# AtmelSMD328NRF.net
KiCad netlist of a schematic drawn in EAGLE
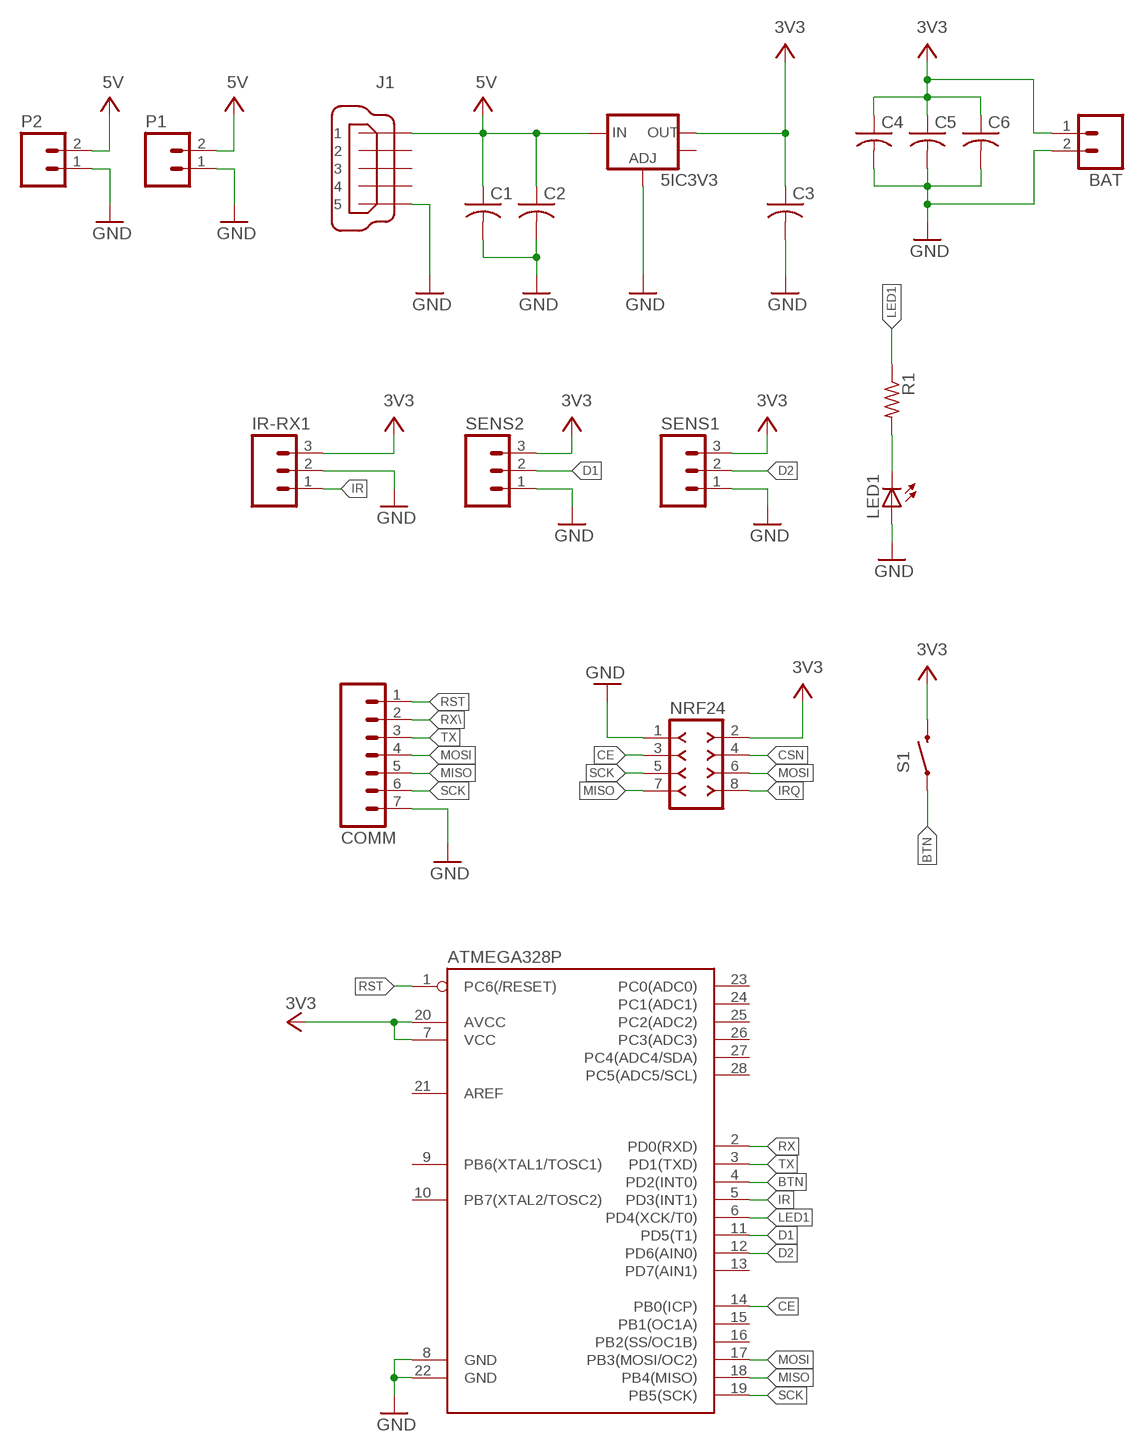
[diagram p0: schematic, sheet 1]

(export (version "E")
  (design (tool "Eeschema 10.0.6"))
  (components
    (comp (ref "5IC3V3")
      (value "V_REG_LM1117SOT223")
      (footprint "eagle-import:SOT223")
      (libsource (lib "eagle-import") (part "V_REG_LM1117SOT223"))
    )
    (comp (ref "ATMEGA328P")
      (value "ATMEGA328P_PDIP")
      (footprint "eagle-import:DIL28-3")
      (libsource (lib "eagle-import") (part "ATMEGA328P_PDIP"))
    )
    (comp (ref "BAT")
      (value "M02PTH")
      (footprint "eagle-import:1X02")
      (libsource (lib "eagle-import") (part "M02PTH"))
    )
    (comp (ref "C1")
      (value "C-USC0805")
      (footprint "eagle-import:C0805")
      (libsource (lib "eagle-import") (part "C-USC0805"))
    )
    (comp (ref "C2")
      (value "C-USC0805")
      (footprint "eagle-import:C0805")
      (libsource (lib "eagle-import") (part "C-USC0805"))
    )
    (comp (ref "C3")
      (value "C-USC0805")
      (footprint "eagle-import:C0805")
      (libsource (lib "eagle-import") (part "C-USC0805"))
    )
    (comp (ref "C4")
      (value "C-USC0805")
      (footprint "eagle-import:C0805")
      (libsource (lib "eagle-import") (part "C-USC0805"))
    )
    (comp (ref "C5")
      (value "C-USC0805")
      (footprint "eagle-import:C0805")
      (libsource (lib "eagle-import") (part "C-USC0805"))
    )
    (comp (ref "C6")
      (value "C-USC0805")
      (footprint "eagle-import:C0805")
      (libsource (lib "eagle-import") (part "C-USC0805"))
    )
    (comp (ref "COMM")
      (value "M07")
      (footprint "eagle-import:1X07")
      (libsource (lib "eagle-import") (part "M07"))
    )
    (comp (ref "IR-RX1")
      (value "M03PTH")
      (footprint "eagle-import:1X03")
      (libsource (lib "eagle-import") (part "M03PTH"))
    )
    (comp (ref "J1")
      (value "MICRO-USB-ZX62R-B-5P")
      (footprint "eagle-import:ZX62R-B-5P")
      (libsource (lib "eagle-import") (part "MICRO-USB-ZX62R-B-5P"))
    )
    (comp (ref "LED1")
      (value "LEDCHIPLED_0805")
      (footprint "eagle-import:CHIPLED_0805")
      (libsource (lib "eagle-import") (part "LEDCHIPLED_0805"))
    )
    (comp (ref "NRF24")
      (value "F-2X04-DIL-100")
      (footprint "eagle-import:DIL-100-2X04")
      (libsource (lib "eagle-import") (part "F-2X04-DIL-100"))
    )
    (comp (ref "P1")
      (value "M02PTH")
      (footprint "eagle-import:1X02")
      (libsource (lib "eagle-import") (part "M02PTH"))
    )
    (comp (ref "P2")
      (value "M02PTH")
      (footprint "eagle-import:1X02")
      (libsource (lib "eagle-import") (part "M02PTH"))
    )
    (comp (ref "R1")
      (value "R-US_R0805")
      (footprint "eagle-import:R0805")
      (libsource (lib "eagle-import") (part "R-US_R0805"))
    )
    (comp (ref "S1")
      (value "SWITCH-MOMENTARY-2SMD-1101NE")
      (footprint "eagle-import:TACTILE-SWITCH-1101NE")
      (libsource (lib "eagle-import") (part "SWITCH-MOMENTARY-2SMD-1101NE"))
    )
    (comp (ref "SENS1")
      (value "M03PTH")
      (footprint "eagle-import:1X03")
      (libsource (lib "eagle-import") (part "M03PTH"))
    )
    (comp (ref "SENS2")
      (value "M03PTH")
      (footprint "eagle-import:1X03")
      (libsource (lib "eagle-import") (part "M03PTH"))
    )
  )
  (nets
    (net (code "1") (name "3V3") (class "Default")
      (node (ref "5IC3V3") (pin "2") (pinfunction "OUT_2") (pintype "output"))
      (node (ref "ATMEGA328P") (pin "20") (pinfunction "AVCC_20") (pintype "bidirectional"))
      (node (ref "ATMEGA328P") (pin "7") (pinfunction "VCC_7") (pintype "bidirectional"))
      (node (ref "BAT") (pin "1") (pinfunction "1_1") (pintype "passive"))
      (node (ref "C3") (pin "1") (pinfunction "1_1") (pintype "passive"))
      (node (ref "C4") (pin "1") (pinfunction "1_1") (pintype "passive"))
      (node (ref "C5") (pin "1") (pinfunction "1_1") (pintype "passive"))
      (node (ref "C6") (pin "1") (pinfunction "1_1") (pintype "passive"))
      (node (ref "IR-RX1") (pin "3") (pinfunction "3_3") (pintype "passive"))
      (node (ref "NRF24") (pin "2") (pinfunction "2_2") (pintype "passive"))
      (node (ref "S1") (pin "2") (pinfunction "2_2") (pintype "passive"))
      (node (ref "SENS1") (pin "3") (pinfunction "3_3") (pintype "passive"))
      (node (ref "SENS2") (pin "3") (pinfunction "3_3") (pintype "passive"))
    )
    (net (code "2") (name "5V") (class "Default")
      (node (ref "5IC3V3") (pin "3") (pinfunction "IN_3") (pintype "input"))
      (node (ref "C1") (pin "1") (pinfunction "1_1") (pintype "passive"))
      (node (ref "C2") (pin "1") (pinfunction "1_1") (pintype "passive"))
      (node (ref "J1") (pin "1") (pinfunction "1_1") (pintype "input"))
      (node (ref "P1") (pin "2") (pinfunction "2_2") (pintype "passive"))
      (node (ref "P2") (pin "2") (pinfunction "2_2") (pintype "passive"))
    )
    (net (code "3") (name "BTN") (class "Default")
      (node (ref "ATMEGA328P") (pin "4") (pinfunction "PD2(INT0)_4") (pintype "bidirectional"))
      (node (ref "S1") (pin "1") (pinfunction "1_1") (pintype "passive"))
    )
    (net (code "4") (name "CE") (class "Default")
      (node (ref "ATMEGA328P") (pin "14") (pinfunction "PB0(ICP)_14") (pintype "bidirectional"))
      (node (ref "NRF24") (pin "3") (pinfunction "3_3") (pintype "passive"))
    )
    (net (code "5") (name "CSN") (class "Default")
      (node (ref "NRF24") (pin "4") (pinfunction "4_4") (pintype "passive"))
    )
    (net (code "6") (name "D1") (class "Default")
      (node (ref "ATMEGA328P") (pin "11") (pinfunction "PD5(T1)_11") (pintype "bidirectional"))
      (node (ref "SENS2") (pin "2") (pinfunction "2_2") (pintype "passive"))
    )
    (net (code "7") (name "D2") (class "Default")
      (node (ref "ATMEGA328P") (pin "12") (pinfunction "PD6(AIN0)_12") (pintype "bidirectional"))
      (node (ref "SENS1") (pin "2") (pinfunction "2_2") (pintype "passive"))
    )
    (net (code "8") (name "GND") (class "Default")
      (node (ref "5IC3V3") (pin "1") (pinfunction "ADJ_1") (pintype "input"))
      (node (ref "ATMEGA328P") (pin "22") (pinfunction "GND_22") (pintype "bidirectional"))
      (node (ref "ATMEGA328P") (pin "8") (pinfunction "GND_8") (pintype "bidirectional"))
      (node (ref "BAT") (pin "2") (pinfunction "2_2") (pintype "passive"))
      (node (ref "C1") (pin "2") (pinfunction "2_2") (pintype "passive"))
      (node (ref "C2") (pin "2") (pinfunction "2_2") (pintype "passive"))
      (node (ref "C3") (pin "2") (pinfunction "2_2") (pintype "passive"))
      (node (ref "C4") (pin "2") (pinfunction "2_2") (pintype "passive"))
      (node (ref "C5") (pin "2") (pinfunction "2_2") (pintype "passive"))
      (node (ref "C6") (pin "2") (pinfunction "2_2") (pintype "passive"))
      (node (ref "COMM") (pin "7") (pinfunction "7_7") (pintype "passive"))
      (node (ref "IR-RX1") (pin "2") (pinfunction "2_2") (pintype "passive"))
      (node (ref "J1") (pin "5") (pinfunction "5_5") (pintype "input"))
      (node (ref "LED1") (pin "A") (pinfunction "A_A") (pintype "passive"))
      (node (ref "NRF24") (pin "1") (pinfunction "1_1") (pintype "passive"))
      (node (ref "P1") (pin "1") (pinfunction "1_1") (pintype "passive"))
      (node (ref "P2") (pin "1") (pinfunction "1_1") (pintype "passive"))
      (node (ref "SENS1") (pin "1") (pinfunction "1_1") (pintype "passive"))
      (node (ref "SENS2") (pin "1") (pinfunction "1_1") (pintype "passive"))
    )
    (net (code "9") (name "IR") (class "Default")
      (node (ref "ATMEGA328P") (pin "5") (pinfunction "PD3(INT1)_5") (pintype "bidirectional"))
      (node (ref "IR-RX1") (pin "1") (pinfunction "1_1") (pintype "passive"))
    )
    (net (code "10") (name "IRQ") (class "Default")
      (node (ref "NRF24") (pin "8") (pinfunction "8_8") (pintype "passive"))
    )
    (net (code "11") (name "LED1") (class "Default")
      (node (ref "ATMEGA328P") (pin "6") (pinfunction "PD4(XCK/T0)_6") (pintype "bidirectional"))
      (node (ref "R1") (pin "1") (pinfunction "1_1") (pintype "passive"))
    )
    (net (code "12") (name "MISO") (class "Default")
      (node (ref "ATMEGA328P") (pin "18") (pinfunction "PB4(MISO)_18") (pintype "bidirectional"))
      (node (ref "COMM") (pin "5") (pinfunction "5_5") (pintype "passive"))
      (node (ref "NRF24") (pin "7") (pinfunction "7_7") (pintype "passive"))
    )
    (net (code "13") (name "MOSI") (class "Default")
      (node (ref "ATMEGA328P") (pin "17") (pinfunction "PB3(MOSI/OC2)_17") (pintype "bidirectional"))
      (node (ref "COMM") (pin "4") (pinfunction "4_4") (pintype "passive"))
      (node (ref "NRF24") (pin "6") (pinfunction "6_6") (pintype "passive"))
    )
    (net (code "14") (name "Net-(LED1-PadC)") (class "Default")
      (node (ref "LED1") (pin "C") (pinfunction "C_C") (pintype "passive"))
      (node (ref "R1") (pin "2") (pinfunction "2_2") (pintype "passive"))
    )
    (net (code "15") (name "RST") (class "Default")
      (node (ref "ATMEGA328P") (pin "1") (pinfunction "PC6(/RESET)_1") (pintype "bidirectional"))
      (node (ref "COMM") (pin "1") (pinfunction "1_1") (pintype "passive"))
    )
    (net (code "16") (name "RX") (class "Default")
      (node (ref "ATMEGA328P") (pin "2") (pinfunction "PD0(RXD)_2") (pintype "bidirectional"))
    )
    (net (code "17") (name "RX\\") (class "Default")
      (node (ref "COMM") (pin "2") (pinfunction "2_2") (pintype "passive"))
    )
    (net (code "18") (name "SCK") (class "Default")
      (node (ref "ATMEGA328P") (pin "19") (pinfunction "PB5(SCK)_19") (pintype "bidirectional"))
      (node (ref "COMM") (pin "6") (pinfunction "6_6") (pintype "passive"))
      (node (ref "NRF24") (pin "5") (pinfunction "5_5") (pintype "passive"))
    )
    (net (code "19") (name "TX") (class "Default")
      (node (ref "ATMEGA328P") (pin "3") (pinfunction "PD1(TXD)_3") (pintype "bidirectional"))
      (node (ref "COMM") (pin "3") (pinfunction "3_3") (pintype "passive"))
    )
    (net (code "20") (name "unconnected-(5IC3V3-OUT-Pad4)") (class "Default")
      (node (ref "5IC3V3") (pin "4") (pinfunction "OUT_4") (pintype "output"))
    )
    (net (code "21") (name "unconnected-(ATMEGA328P-AREF-Pad21)") (class "Default")
      (node (ref "ATMEGA328P") (pin "21") (pinfunction "AREF_21") (pintype "bidirectional"))
    )
    (net (code "22") (name "unconnected-(ATMEGA328P-PB1(OC1A)-Pad15)") (class "Default")
      (node (ref "ATMEGA328P") (pin "15") (pinfunction "PB1(OC1A)_15") (pintype "bidirectional"))
    )
    (net (code "23") (name "unconnected-(ATMEGA328P-PB2(SS{slash}OC1B)-Pad16)") (class "Default")
      (node (ref "ATMEGA328P") (pin "16") (pinfunction "PB2(SS/OC1B)_16") (pintype "bidirectional"))
    )
    (net (code "24") (name "unconnected-(ATMEGA328P-PB6(XTAL1{slash}TOSC1)-Pad9)") (class "Default")
      (node (ref "ATMEGA328P") (pin "9") (pinfunction "PB6(XTAL1/TOSC1)_9") (pintype "bidirectional"))
    )
    (net (code "25") (name "unconnected-(ATMEGA328P-PB7(XTAL2{slash}TOSC2)-Pad10)") (class "Default")
      (node (ref "ATMEGA328P") (pin "10") (pinfunction "PB7(XTAL2/TOSC2)_10") (pintype "bidirectional"))
    )
    (net (code "26") (name "unconnected-(ATMEGA328P-PC0(ADC0)-Pad23)") (class "Default")
      (node (ref "ATMEGA328P") (pin "23") (pinfunction "PC0(ADC0)_23") (pintype "bidirectional"))
    )
    (net (code "27") (name "unconnected-(ATMEGA328P-PC1(ADC1)-Pad24)") (class "Default")
      (node (ref "ATMEGA328P") (pin "24") (pinfunction "PC1(ADC1)_24") (pintype "bidirectional"))
    )
    (net (code "28") (name "unconnected-(ATMEGA328P-PC2(ADC2)-Pad25)") (class "Default")
      (node (ref "ATMEGA328P") (pin "25") (pinfunction "PC2(ADC2)_25") (pintype "bidirectional"))
    )
    (net (code "29") (name "unconnected-(ATMEGA328P-PC3(ADC3)-Pad26)") (class "Default")
      (node (ref "ATMEGA328P") (pin "26") (pinfunction "PC3(ADC3)_26") (pintype "bidirectional"))
    )
    (net (code "30") (name "unconnected-(ATMEGA328P-PC4(ADC4{slash}SDA)-Pad27)") (class "Default")
      (node (ref "ATMEGA328P") (pin "27") (pinfunction "PC4(ADC4/SDA)_27") (pintype "bidirectional"))
    )
    (net (code "31") (name "unconnected-(ATMEGA328P-PC5(ADC5{slash}SCL)-Pad28)") (class "Default")
      (node (ref "ATMEGA328P") (pin "28") (pinfunction "PC5(ADC5/SCL)_28") (pintype "bidirectional"))
    )
    (net (code "32") (name "unconnected-(ATMEGA328P-PD7(AIN1)-Pad13)") (class "Default")
      (node (ref "ATMEGA328P") (pin "13") (pinfunction "PD7(AIN1)_13") (pintype "bidirectional"))
    )
    (net (code "33") (name "unconnected-(J1-Pad2)") (class "Default")
      (node (ref "J1") (pin "2") (pinfunction "2_2") (pintype "input"))
    )
    (net (code "34") (name "unconnected-(J1-Pad3)") (class "Default")
      (node (ref "J1") (pin "3") (pinfunction "3_3") (pintype "input"))
    )
    (net (code "35") (name "unconnected-(J1-Pad4)") (class "Default")
      (node (ref "J1") (pin "4") (pinfunction "4_4") (pintype "input"))
    )
  )
)
